# esp32_breakout.net
KiCad netlist of a schematic drawn in EAGLE
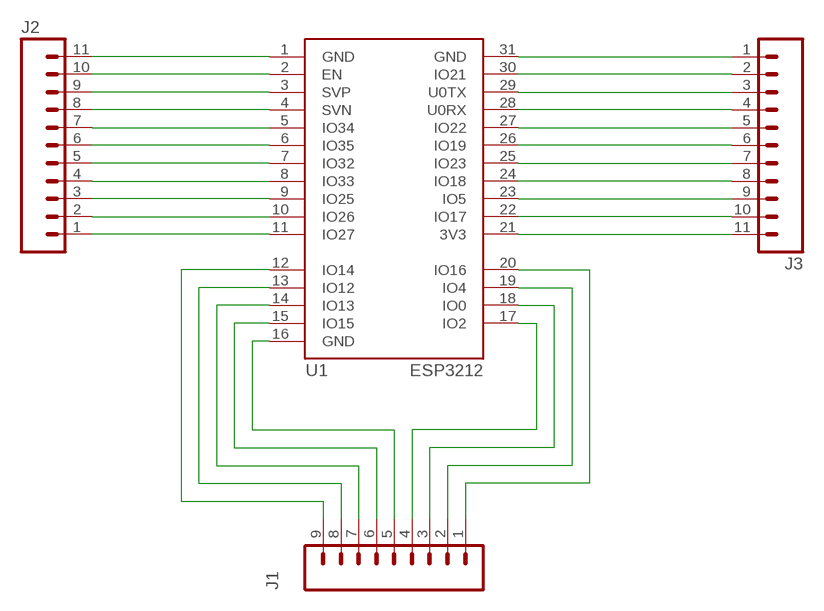
[diagram p0: schematic, sheet 1]

(export (version "E")
  (design (tool "Eeschema 10.0.6"))
  (components
    (comp (ref "J1")
      (value "M09")
      (footprint "eagle-import:1X09")
      (libsource (lib "eagle-import") (part "M09"))
    )
    (comp (ref "J2")
      (value "M11PTH")
      (footprint "eagle-import:1X11")
      (libsource (lib "eagle-import") (part "M11PTH"))
    )
    (comp (ref "J3")
      (value "M11PTH")
      (footprint "eagle-import:1X11")
      (libsource (lib "eagle-import") (part "M11PTH"))
    )
    (comp (ref "U1")
      (value "ESP3212")
      (footprint "eagle-import:ESP3212")
      (libsource (lib "eagle-import") (part "ESP3212"))
    )
  )
  (nets
    (net (code "1") (name "Net-(J1-Pad5)") (class "Default")
      (node (ref "J1") (pin "5") (pinfunction "5_5") (pintype "passive"))
      (node (ref "U1") (pin "16") (pinfunction "GND_16") (pintype "power_in"))
    )
    (net (code "2") (name "Net-(J2-Pad11)") (class "Default")
      (node (ref "J2") (pin "11") (pinfunction "11_11") (pintype "passive"))
      (node (ref "U1") (pin "1") (pinfunction "GND_1") (pintype "power_in"))
    )
    (net (code "3") (name "Net-(J3-Pad1)") (class "Default")
      (node (ref "J3") (pin "1") (pinfunction "1_1") (pintype "passive"))
      (node (ref "U1") (pin "31") (pinfunction "GND_31") (pintype "power_in"))
    )
    (net (code "4") (name "Net-(U1-3V3)") (class "Default")
      (node (ref "J3") (pin "11") (pinfunction "11_11") (pintype "passive"))
      (node (ref "U1") (pin "21") (pinfunction "3V3_21") (pintype "power_in"))
    )
    (net (code "5") (name "Net-(U1-EN)") (class "Default")
      (node (ref "J2") (pin "10") (pinfunction "10_10") (pintype "passive"))
      (node (ref "U1") (pin "2") (pinfunction "EN_2") (pintype "input"))
    )
    (net (code "6") (name "Net-(U1-IO0)") (class "Default")
      (node (ref "J1") (pin "3") (pinfunction "3_3") (pintype "passive"))
      (node (ref "U1") (pin "18") (pinfunction "IO0_18") (pintype "bidirectional"))
    )
    (net (code "7") (name "Net-(U1-IO2)") (class "Default")
      (node (ref "J1") (pin "4") (pinfunction "4_4") (pintype "passive"))
      (node (ref "U1") (pin "17") (pinfunction "IO2_17") (pintype "bidirectional"))
    )
    (net (code "8") (name "Net-(U1-IO4)") (class "Default")
      (node (ref "J1") (pin "2") (pinfunction "2_2") (pintype "passive"))
      (node (ref "U1") (pin "19") (pinfunction "IO4_19") (pintype "bidirectional"))
    )
    (net (code "9") (name "Net-(U1-IO5)") (class "Default")
      (node (ref "J3") (pin "9") (pinfunction "9_9") (pintype "passive"))
      (node (ref "U1") (pin "23") (pinfunction "IO5_23") (pintype "bidirectional"))
    )
    (net (code "10") (name "Net-(U1-IO12)") (class "Default")
      (node (ref "J1") (pin "8") (pinfunction "8_8") (pintype "passive"))
      (node (ref "U1") (pin "13") (pinfunction "IO12_13") (pintype "bidirectional"))
    )
    (net (code "11") (name "Net-(U1-IO13)") (class "Default")
      (node (ref "J1") (pin "7") (pinfunction "7_7") (pintype "passive"))
      (node (ref "U1") (pin "14") (pinfunction "IO13_14") (pintype "bidirectional"))
    )
    (net (code "12") (name "Net-(U1-IO14)") (class "Default")
      (node (ref "J1") (pin "9") (pinfunction "9_9") (pintype "passive"))
      (node (ref "U1") (pin "12") (pinfunction "IO14_12") (pintype "bidirectional"))
    )
    (net (code "13") (name "Net-(U1-IO15)") (class "Default")
      (node (ref "J1") (pin "6") (pinfunction "6_6") (pintype "passive"))
      (node (ref "U1") (pin "15") (pinfunction "IO15_15") (pintype "bidirectional"))
    )
    (net (code "14") (name "Net-(U1-IO16)") (class "Default")
      (node (ref "J1") (pin "1") (pinfunction "1_1") (pintype "passive"))
      (node (ref "U1") (pin "20") (pinfunction "IO16_20") (pintype "bidirectional"))
    )
    (net (code "15") (name "Net-(U1-IO17)") (class "Default")
      (node (ref "J3") (pin "10") (pinfunction "10_10") (pintype "passive"))
      (node (ref "U1") (pin "22") (pinfunction "IO17_22") (pintype "bidirectional"))
    )
    (net (code "16") (name "Net-(U1-IO18)") (class "Default")
      (node (ref "J3") (pin "8") (pinfunction "8_8") (pintype "passive"))
      (node (ref "U1") (pin "24") (pinfunction "IO18_24") (pintype "bidirectional"))
    )
    (net (code "17") (name "Net-(U1-IO19)") (class "Default")
      (node (ref "J3") (pin "6") (pinfunction "6_6") (pintype "passive"))
      (node (ref "U1") (pin "26") (pinfunction "IO19_26") (pintype "bidirectional"))
    )
    (net (code "18") (name "Net-(U1-IO21)") (class "Default")
      (node (ref "J3") (pin "2") (pinfunction "2_2") (pintype "passive"))
      (node (ref "U1") (pin "30") (pinfunction "IO21_30") (pintype "bidirectional"))
    )
    (net (code "19") (name "Net-(U1-IO22)") (class "Default")
      (node (ref "J3") (pin "5") (pinfunction "5_5") (pintype "passive"))
      (node (ref "U1") (pin "27") (pinfunction "IO22_27") (pintype "bidirectional"))
    )
    (net (code "20") (name "Net-(U1-IO23)") (class "Default")
      (node (ref "J3") (pin "7") (pinfunction "7_7") (pintype "passive"))
      (node (ref "U1") (pin "25") (pinfunction "IO23_25") (pintype "bidirectional"))
    )
    (net (code "21") (name "Net-(U1-IO25)") (class "Default")
      (node (ref "J2") (pin "3") (pinfunction "3_3") (pintype "passive"))
      (node (ref "U1") (pin "9") (pinfunction "IO25_9") (pintype "bidirectional"))
    )
    (net (code "22") (name "Net-(U1-IO26)") (class "Default")
      (node (ref "J2") (pin "2") (pinfunction "2_2") (pintype "passive"))
      (node (ref "U1") (pin "10") (pinfunction "IO26_10") (pintype "bidirectional"))
    )
    (net (code "23") (name "Net-(U1-IO27)") (class "Default")
      (node (ref "J2") (pin "1") (pinfunction "1_1") (pintype "passive"))
      (node (ref "U1") (pin "11") (pinfunction "IO27_11") (pintype "bidirectional"))
    )
    (net (code "24") (name "Net-(U1-IO32)") (class "Default")
      (node (ref "J2") (pin "5") (pinfunction "5_5") (pintype "passive"))
      (node (ref "U1") (pin "7") (pinfunction "IO32_7") (pintype "bidirectional"))
    )
    (net (code "25") (name "Net-(U1-IO33)") (class "Default")
      (node (ref "J2") (pin "4") (pinfunction "4_4") (pintype "passive"))
      (node (ref "U1") (pin "8") (pinfunction "IO33_8") (pintype "bidirectional"))
    )
    (net (code "26") (name "Net-(U1-IO34)") (class "Default")
      (node (ref "J2") (pin "7") (pinfunction "7_7") (pintype "passive"))
      (node (ref "U1") (pin "5") (pinfunction "IO34_5") (pintype "bidirectional"))
    )
    (net (code "27") (name "Net-(U1-IO35)") (class "Default")
      (node (ref "J2") (pin "6") (pinfunction "6_6") (pintype "passive"))
      (node (ref "U1") (pin "6") (pinfunction "IO35_6") (pintype "bidirectional"))
    )
    (net (code "28") (name "Net-(U1-SVN)") (class "Default")
      (node (ref "J2") (pin "8") (pinfunction "8_8") (pintype "passive"))
      (node (ref "U1") (pin "4") (pinfunction "SVN_4") (pintype "bidirectional"))
    )
    (net (code "29") (name "Net-(U1-SVP)") (class "Default")
      (node (ref "J2") (pin "9") (pinfunction "9_9") (pintype "passive"))
      (node (ref "U1") (pin "3") (pinfunction "SVP_3") (pintype "bidirectional"))
    )
    (net (code "30") (name "Net-(U1-U0RX)") (class "Default")
      (node (ref "J3") (pin "4") (pinfunction "4_4") (pintype "passive"))
      (node (ref "U1") (pin "28") (pinfunction "U0RX_28") (pintype "bidirectional"))
    )
    (net (code "31") (name "Net-(U1-U0TX)") (class "Default")
      (node (ref "J3") (pin "3") (pinfunction "3_3") (pintype "passive"))
      (node (ref "U1") (pin "29") (pinfunction "U0TX_29") (pintype "bidirectional"))
    )
  )
)
